# DSA.net
KiCad netlist of a schematic drawn in Altium Designer
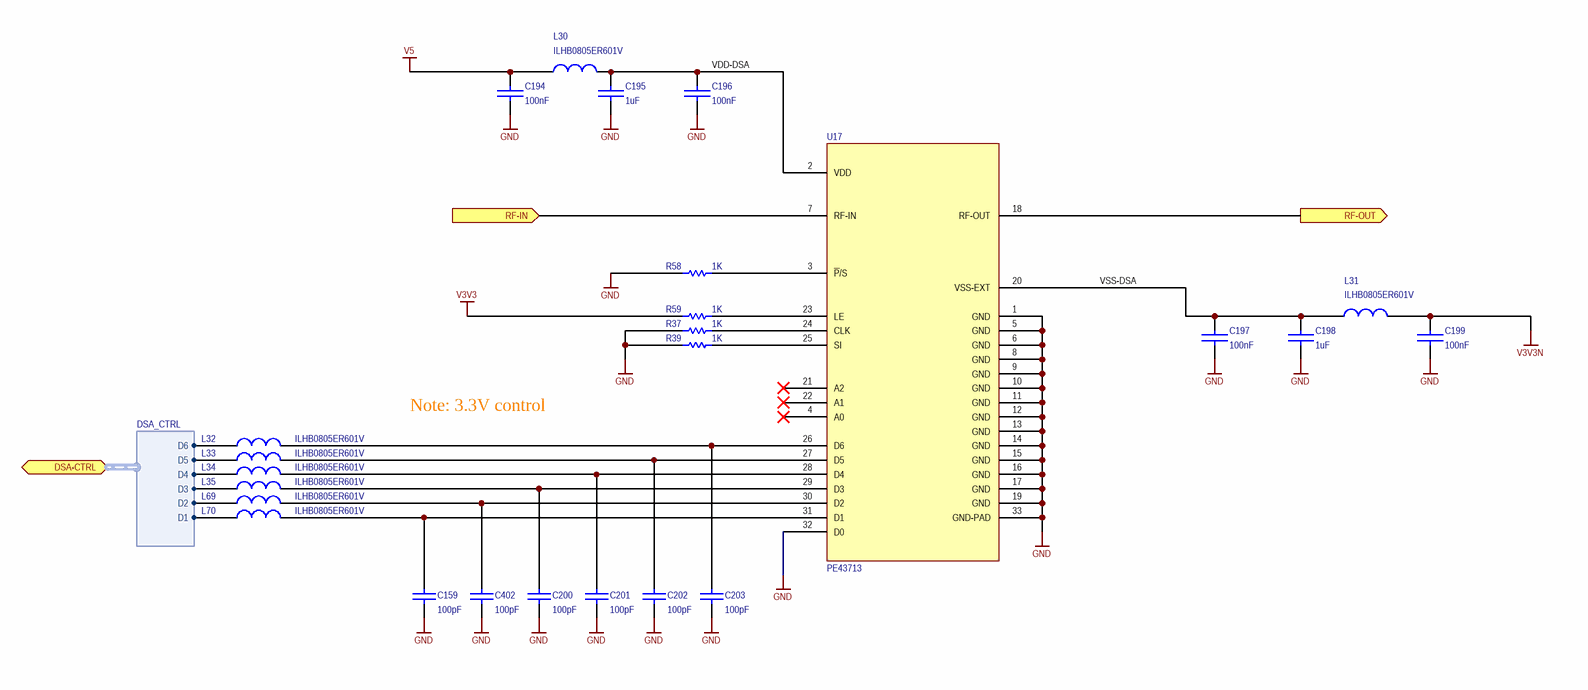
[diagram p0: DSA.SchDoc]

(export (version "E")
  (design (tool "Eeschema 10.0.6"))
  (components
    (comp (ref "C159")
      (value "100pF")
      (footprint "generic:0402")
      (description "Ceramic Capacitor 100pF ±1% 25V NP0 0402")
      (fields (field (name "VOLTAGE") "25V") (field (name "MANUFACTURER") "Kemet"))
      (libsource (lib "PopRock") (part "CAP 0402"))
    )
    (comp (ref "C194")
      (value "100nF")
      (footprint "generic:0402")
      (description "Ceramic Capacitor 100nF ±10% 16V X7R 0402")
      (fields (field (name "MANUFACTURER") "Murata") (field (name "VOLTAGE") "16V"))
      (libsource (lib "*") (part "CAP"))
    )
    (comp (ref "C195")
      (value "1uF")
      (footprint "generic:0402")
      (description "Ceramic Capacitor 1uF ±10% 10V X5R 0402")
      (fields (field (name "MANUFACTURER") "Murata") (field (name "TOLERANCE") "±10%"))
      (libsource (lib "*") (part "CAP"))
    )
    (comp (ref "C196")
      (value "100nF")
      (footprint "generic:0402")
      (description "Ceramic Capacitor 100nF ±10% 16V X7R 0402")
      (fields (field (name "MANUFACTURER") "Murata") (field (name "VOLTAGE") "16V"))
      (libsource (lib "*") (part "CAP"))
    )
    (comp (ref "C197")
      (value "100nF")
      (footprint "generic:0402")
      (description "Ceramic Capacitor 100nF ±10% 16V X7R 0402")
      (fields (field (name "MANUFACTURER") "Murata") (field (name "VOLTAGE") "16V"))
      (libsource (lib "*") (part "CAP"))
    )
    (comp (ref "C198")
      (value "1uF")
      (footprint "generic:0402")
      (description "Ceramic Capacitor 1uF ±10% 10V X5R 0402")
      (fields (field (name "MANUFACTURER") "Murata") (field (name "TOLERANCE") "±10%"))
      (libsource (lib "*") (part "CAP"))
    )
    (comp (ref "C199")
      (value "100nF")
      (footprint "generic:0402")
      (description "Ceramic Capacitor 100nF ±10% 16V X7R 0402")
      (fields (field (name "MANUFACTURER") "Murata") (field (name "VOLTAGE") "16V"))
      (libsource (lib "*") (part "CAP"))
    )
    (comp (ref "C200")
      (value "100pF")
      (footprint "generic:0402")
      (description "Ceramic Capacitor 100pF ±1% 25V NP0 0402")
      (fields (field (name "VOLTAGE") "25V") (field (name "MANUFACTURER") "Kemet"))
      (libsource (lib "PopRock") (part "CAP 0402"))
    )
    (comp (ref "C201")
      (value "100pF")
      (footprint "generic:0402")
      (description "Ceramic Capacitor 100pF ±1% 25V NP0 0402")
      (fields (field (name "VOLTAGE") "25V") (field (name "MANUFACTURER") "Kemet"))
      (libsource (lib "PopRock") (part "CAP 0402"))
    )
    (comp (ref "C202")
      (value "100pF")
      (footprint "generic:0402")
      (description "Ceramic Capacitor 100pF ±1% 25V NP0 0402")
      (fields (field (name "VOLTAGE") "25V") (field (name "MANUFACTURER") "Kemet"))
      (libsource (lib "PopRock") (part "CAP 0402"))
    )
    (comp (ref "C203")
      (value "100pF")
      (footprint "generic:0402")
      (description "Ceramic Capacitor 100pF ±1% 25V NP0 0402")
      (fields (field (name "VOLTAGE") "25V") (field (name "MANUFACTURER") "Kemet"))
      (libsource (lib "PopRock") (part "CAP 0402"))
    )
    (comp (ref "C402")
      (value "100pF")
      (footprint "generic:0402")
      (description "Ceramic Capacitor 100pF ±1% 25V NP0 0402")
      (fields (field (name "VOLTAGE") "25V") (field (name "MANUFACTURER") "Kemet"))
      (libsource (lib "PopRock") (part "CAP 0402"))
    )
    (comp (ref "L30")
      (value "ILHB0805ER601V")
      (footprint "0805")
      (description "Ferrite Bead 600-Ohm @ 100MHz 2A 0805")
      (fields (field (name "MANUFACTURER") "Vishay Dale") (field (name "TOLERANCE") "±25%"))
      (libsource (lib "*") (part "INDUCTANCE1"))
    )
    (comp (ref "L31")
      (value "ILHB0805ER601V")
      (footprint "0805")
      (description "Ferrite Bead 600-Ohm @ 100MHz 2A 0805")
      (fields (field (name "MANUFACTURER") "Vishay Dale") (field (name "TOLERANCE") "±25%"))
      (libsource (lib "") (part "INDUCTANCE1_1"))
    )
    (comp (ref "L32")
      (value "ILHB0805ER601V")
      (footprint "0805")
      (description "Ferrite Bead 600-Ohm @ 100MHz 2A 0805")
      (fields (field (name "MANUFACTURER") "Vishay Dale") (field (name "TOLERANCE") "±25%"))
      (libsource (lib "*") (part "INDUCTANCE1"))
    )
    (comp (ref "L33")
      (value "ILHB0805ER601V")
      (footprint "0805")
      (description "Ferrite Bead 600-Ohm @ 100MHz 2A 0805")
      (fields (field (name "MANUFACTURER") "Vishay Dale") (field (name "TOLERANCE") "±25%"))
      (libsource (lib "*") (part "INDUCTANCE1"))
    )
    (comp (ref "L34")
      (value "ILHB0805ER601V")
      (footprint "0805")
      (description "Ferrite Bead 600-Ohm @ 100MHz 2A 0805")
      (fields (field (name "MANUFACTURER") "Vishay Dale") (field (name "TOLERANCE") "±25%"))
      (libsource (lib "*") (part "INDUCTANCE1"))
    )
    (comp (ref "L35")
      (value "ILHB0805ER601V")
      (footprint "0805")
      (description "Ferrite Bead 600-Ohm @ 100MHz 2A 0805")
      (fields (field (name "MANUFACTURER") "Vishay Dale") (field (name "TOLERANCE") "±25%"))
      (libsource (lib "*") (part "INDUCTANCE1"))
    )
    (comp (ref "L69")
      (value "ILHB0805ER601V")
      (footprint "0805")
      (description "Ferrite Bead 600-Ohm @ 100MHz 2A 0805")
      (fields (field (name "MANUFACTURER") "Vishay Dale") (field (name "TOLERANCE") "±25%"))
      (libsource (lib "*") (part "INDUCTANCE1"))
    )
    (comp (ref "L70")
      (value "ILHB0805ER601V")
      (footprint "0805")
      (description "Ferrite Bead 600-Ohm @ 100MHz 2A 0805")
      (fields (field (name "MANUFACTURER") "Vishay Dale") (field (name "TOLERANCE") "±25%"))
      (libsource (lib "*") (part "INDUCTANCE1"))
    )
    (comp (ref "R37")
      (value "1K")
      (footprint "generic:0402")
      (description "Thick Film Resistor 1k ±1% 0402")
      (fields (field (name "MANUFACTURER") "Yageo") (field (name "TOLERANCE") "±1%"))
      (libsource (lib "Graviton") (part "RES 0402"))
    )
    (comp (ref "R39")
      (value "1K")
      (footprint "generic:0402")
      (description "Thick Film Resistor 1k ±1% 0402")
      (fields (field (name "MANUFACTURER") "Yageo") (field (name "TOLERANCE") "±1%"))
      (libsource (lib "Graviton") (part "RES 0402"))
    )
    (comp (ref "R58")
      (value "1K")
      (footprint "generic:0402")
      (description "Thick Film Resistor 1k ±1% 0402")
      (fields (field (name "MANUFACTURER") "Yageo") (field (name "TOLERANCE") "±1%"))
      (libsource (lib "Graviton") (part "RES 0402"))
    )
    (comp (ref "R59")
      (value "1K")
      (footprint "generic:0402")
      (description "Thick Film Resistor 1k ±1% 0402")
      (fields (field (name "MANUFACTURER") "Yageo") (field (name "TOLERANCE") "±1%"))
      (libsource (lib "Graviton") (part "RES 0402"))
    )
    (comp (ref "U17")
      (value "PE43713")
      (footprint "QFN-PE-32")
      (description "Digital Step Attenuaator, 9kHz-6GHz")
      (fields (field (name "MANUFACTURER") "Peregrine Semiconductor"))
      (libsource (lib "peregrine") (part "PE43713"))
    )
  )
  (nets
    (net (code "2") (name "/D1") (class "Default")
      (node (ref "L70") (pin "2") (pinfunction "2_2") (pintype "passive"))
    )
    (net (code "3") (name "/D2") (class "Default")
      (node (ref "L69") (pin "2") (pinfunction "2_2") (pintype "passive"))
    )
    (net (code "4") (name "/D3") (class "Default")
      (node (ref "L35") (pin "2") (pinfunction "2_2") (pintype "passive"))
    )
    (net (code "5") (name "/D4") (class "Default")
      (node (ref "L34") (pin "2") (pinfunction "2_2") (pintype "passive"))
    )
    (net (code "6") (name "/D5") (class "Default")
      (node (ref "L33") (pin "2") (pinfunction "2_2") (pintype "passive"))
    )
    (net (code "7") (name "/D6") (class "Default")
      (node (ref "L32") (pin "2") (pinfunction "2_2") (pintype "passive"))
    )
    (net (code "8") (name "/RF-IN") (class "Default")
      (node (ref "U17") (pin "7") (pinfunction "RF-IN_7") (pintype "passive"))
    )
    (net (code "9") (name "/RF-OUT") (class "Default")
      (node (ref "U17") (pin "18") (pinfunction "RF-OUT_18") (pintype "passive"))
    )
    (net (code "10") (name "/VDD-DSA") (class "Default")
      (node (ref "C195") (pin "2") (pinfunction "2_2") (pintype "passive"))
      (node (ref "C196") (pin "2") (pinfunction "2_2") (pintype "passive"))
      (node (ref "L30") (pin "1") (pinfunction "1_1") (pintype "passive"))
      (node (ref "U17") (pin "2") (pinfunction "VDD_2") (pintype "passive"))
    )
    (net (code "11") (name "/VSS-DSA") (class "Default")
      (node (ref "C197") (pin "2") (pinfunction "2_2") (pintype "passive"))
      (node (ref "C198") (pin "2") (pinfunction "2_2") (pintype "passive"))
      (node (ref "L31") (pin "1") (pinfunction "1_1") (pintype "passive"))
      (node (ref "U17") (pin "20") (pinfunction "VSS-EXT_20") (pintype "passive"))
    )
    (net (code "13") (name "GND") (class "Default")
      (node (ref "C159") (pin "2") (pinfunction "2_2") (pintype "passive"))
      (node (ref "C194") (pin "1") (pinfunction "1_1") (pintype "passive"))
      (node (ref "C195") (pin "1") (pinfunction "1_1") (pintype "passive"))
      (node (ref "C196") (pin "1") (pinfunction "1_1") (pintype "passive"))
      (node (ref "C197") (pin "1") (pinfunction "1_1") (pintype "passive"))
      (node (ref "C198") (pin "1") (pinfunction "1_1") (pintype "passive"))
      (node (ref "C199") (pin "1") (pinfunction "1_1") (pintype "passive"))
      (node (ref "C200") (pin "2") (pinfunction "2_2") (pintype "passive"))
      (node (ref "C201") (pin "2") (pinfunction "2_2") (pintype "passive"))
      (node (ref "C202") (pin "2") (pinfunction "2_2") (pintype "passive"))
      (node (ref "C203") (pin "2") (pinfunction "2_2") (pintype "passive"))
      (node (ref "C402") (pin "2") (pinfunction "2_2") (pintype "passive"))
      (node (ref "R37") (pin "1") (pinfunction "1_1") (pintype "passive"))
      (node (ref "R39") (pin "1") (pinfunction "1_1") (pintype "passive"))
      (node (ref "R58") (pin "1") (pinfunction "1_1") (pintype "passive"))
      (node (ref "U17") (pin "1") (pinfunction "GND_1") (pintype "passive"))
      (node (ref "U17") (pin "10") (pinfunction "GND_10") (pintype "passive"))
      (node (ref "U17") (pin "11") (pinfunction "GND_11") (pintype "passive"))
      (node (ref "U17") (pin "12") (pinfunction "GND_12") (pintype "passive"))
      (node (ref "U17") (pin "13") (pinfunction "GND_13") (pintype "passive"))
      (node (ref "U17") (pin "14") (pinfunction "GND_14") (pintype "passive"))
      (node (ref "U17") (pin "15") (pinfunction "GND_15") (pintype "passive"))
      (node (ref "U17") (pin "16") (pinfunction "GND_16") (pintype "passive"))
      (node (ref "U17") (pin "17") (pinfunction "GND_17") (pintype "passive"))
      (node (ref "U17") (pin "19") (pinfunction "GND_19") (pintype "passive"))
      (node (ref "U17") (pin "32") (pinfunction "D0_32") (pintype "passive"))
      (node (ref "U17") (pin "33") (pinfunction "GND-PAD_33") (pintype "passive"))
      (node (ref "U17") (pin "5") (pinfunction "GND_5") (pintype "passive"))
      (node (ref "U17") (pin "6") (pinfunction "GND_6") (pintype "passive"))
      (node (ref "U17") (pin "8") (pinfunction "GND_8") (pintype "passive"))
      (node (ref "U17") (pin "9") (pinfunction "GND_9") (pintype "passive"))
    )
    (net (code "14") (name "Net-(U17-CLK)") (class "Default")
      (node (ref "R37") (pin "2") (pinfunction "2_2") (pintype "passive"))
      (node (ref "U17") (pin "24") (pinfunction "CLK_24") (pintype "passive"))
    )
    (net (code "15") (name "Net-(U17-D1)") (class "Default")
      (node (ref "C159") (pin "1") (pinfunction "1_1") (pintype "passive"))
      (node (ref "L70") (pin "1") (pinfunction "1_1") (pintype "passive"))
      (node (ref "U17") (pin "31") (pinfunction "D1_31") (pintype "passive"))
    )
    (net (code "16") (name "Net-(U17-D2)") (class "Default")
      (node (ref "C402") (pin "1") (pinfunction "1_1") (pintype "passive"))
      (node (ref "L69") (pin "1") (pinfunction "1_1") (pintype "passive"))
      (node (ref "U17") (pin "30") (pinfunction "D2_30") (pintype "passive"))
    )
    (net (code "17") (name "Net-(U17-D3)") (class "Default")
      (node (ref "C200") (pin "1") (pinfunction "1_1") (pintype "passive"))
      (node (ref "L35") (pin "1") (pinfunction "1_1") (pintype "passive"))
      (node (ref "U17") (pin "29") (pinfunction "D3_29") (pintype "passive"))
    )
    (net (code "18") (name "Net-(U17-D4)") (class "Default")
      (node (ref "C201") (pin "1") (pinfunction "1_1") (pintype "passive"))
      (node (ref "L34") (pin "1") (pinfunction "1_1") (pintype "passive"))
      (node (ref "U17") (pin "28") (pinfunction "D4_28") (pintype "passive"))
    )
    (net (code "19") (name "Net-(U17-D5)") (class "Default")
      (node (ref "C202") (pin "1") (pinfunction "1_1") (pintype "passive"))
      (node (ref "L33") (pin "1") (pinfunction "1_1") (pintype "passive"))
      (node (ref "U17") (pin "27") (pinfunction "D5_27") (pintype "passive"))
    )
    (net (code "20") (name "Net-(U17-D6)") (class "Default")
      (node (ref "C203") (pin "1") (pinfunction "1_1") (pintype "passive"))
      (node (ref "L32") (pin "1") (pinfunction "1_1") (pintype "passive"))
      (node (ref "U17") (pin "26") (pinfunction "D6_26") (pintype "passive"))
    )
    (net (code "21") (name "Net-(U17-LE)") (class "Default")
      (node (ref "R59") (pin "2") (pinfunction "2_2") (pintype "passive"))
      (node (ref "U17") (pin "23") (pinfunction "LE_23") (pintype "passive"))
    )
    (net (code "22") (name "Net-(U17-SI)") (class "Default")
      (node (ref "R39") (pin "2") (pinfunction "2_2") (pintype "passive"))
      (node (ref "U17") (pin "25") (pinfunction "SI_25") (pintype "passive"))
    )
    (net (code "23") (name "Net-(U17-~{P}{slash}S)") (class "Default")
      (node (ref "R58") (pin "2") (pinfunction "2_2") (pintype "passive"))
      (node (ref "U17") (pin "3") (pinfunction "~{P}/S_3") (pintype "passive"))
    )
    (net (code "24") (name "V3V3") (class "Default")
      (node (ref "R59") (pin "1") (pinfunction "1_1") (pintype "passive"))
    )
    (net (code "25") (name "V3V3N") (class "Default")
      (node (ref "C199") (pin "2") (pinfunction "2_2") (pintype "passive"))
      (node (ref "L31") (pin "2") (pinfunction "2_2") (pintype "passive"))
    )
    (net (code "26") (name "V5") (class "Default")
      (node (ref "C194") (pin "2") (pinfunction "2_2") (pintype "passive"))
      (node (ref "L30") (pin "2") (pinfunction "2_2") (pintype "passive"))
    )
    (net (code "27") (name "unconnected-(U17-A0-Pad4)") (class "Default")
      (node (ref "U17") (pin "4") (pinfunction "A0_4") (pintype "passive+no_connect"))
    )
    (net (code "28") (name "unconnected-(U17-A1-Pad22)") (class "Default")
      (node (ref "U17") (pin "22") (pinfunction "A1_22") (pintype "passive+no_connect"))
    )
    (net (code "29") (name "unconnected-(U17-A2-Pad21)") (class "Default")
      (node (ref "U17") (pin "21") (pinfunction "A2_21") (pintype "passive+no_connect"))
    )
  )
)
